# H-Bridge_Motor_Control_v01.net
KiCad netlist of a schematic drawn in EAGLE
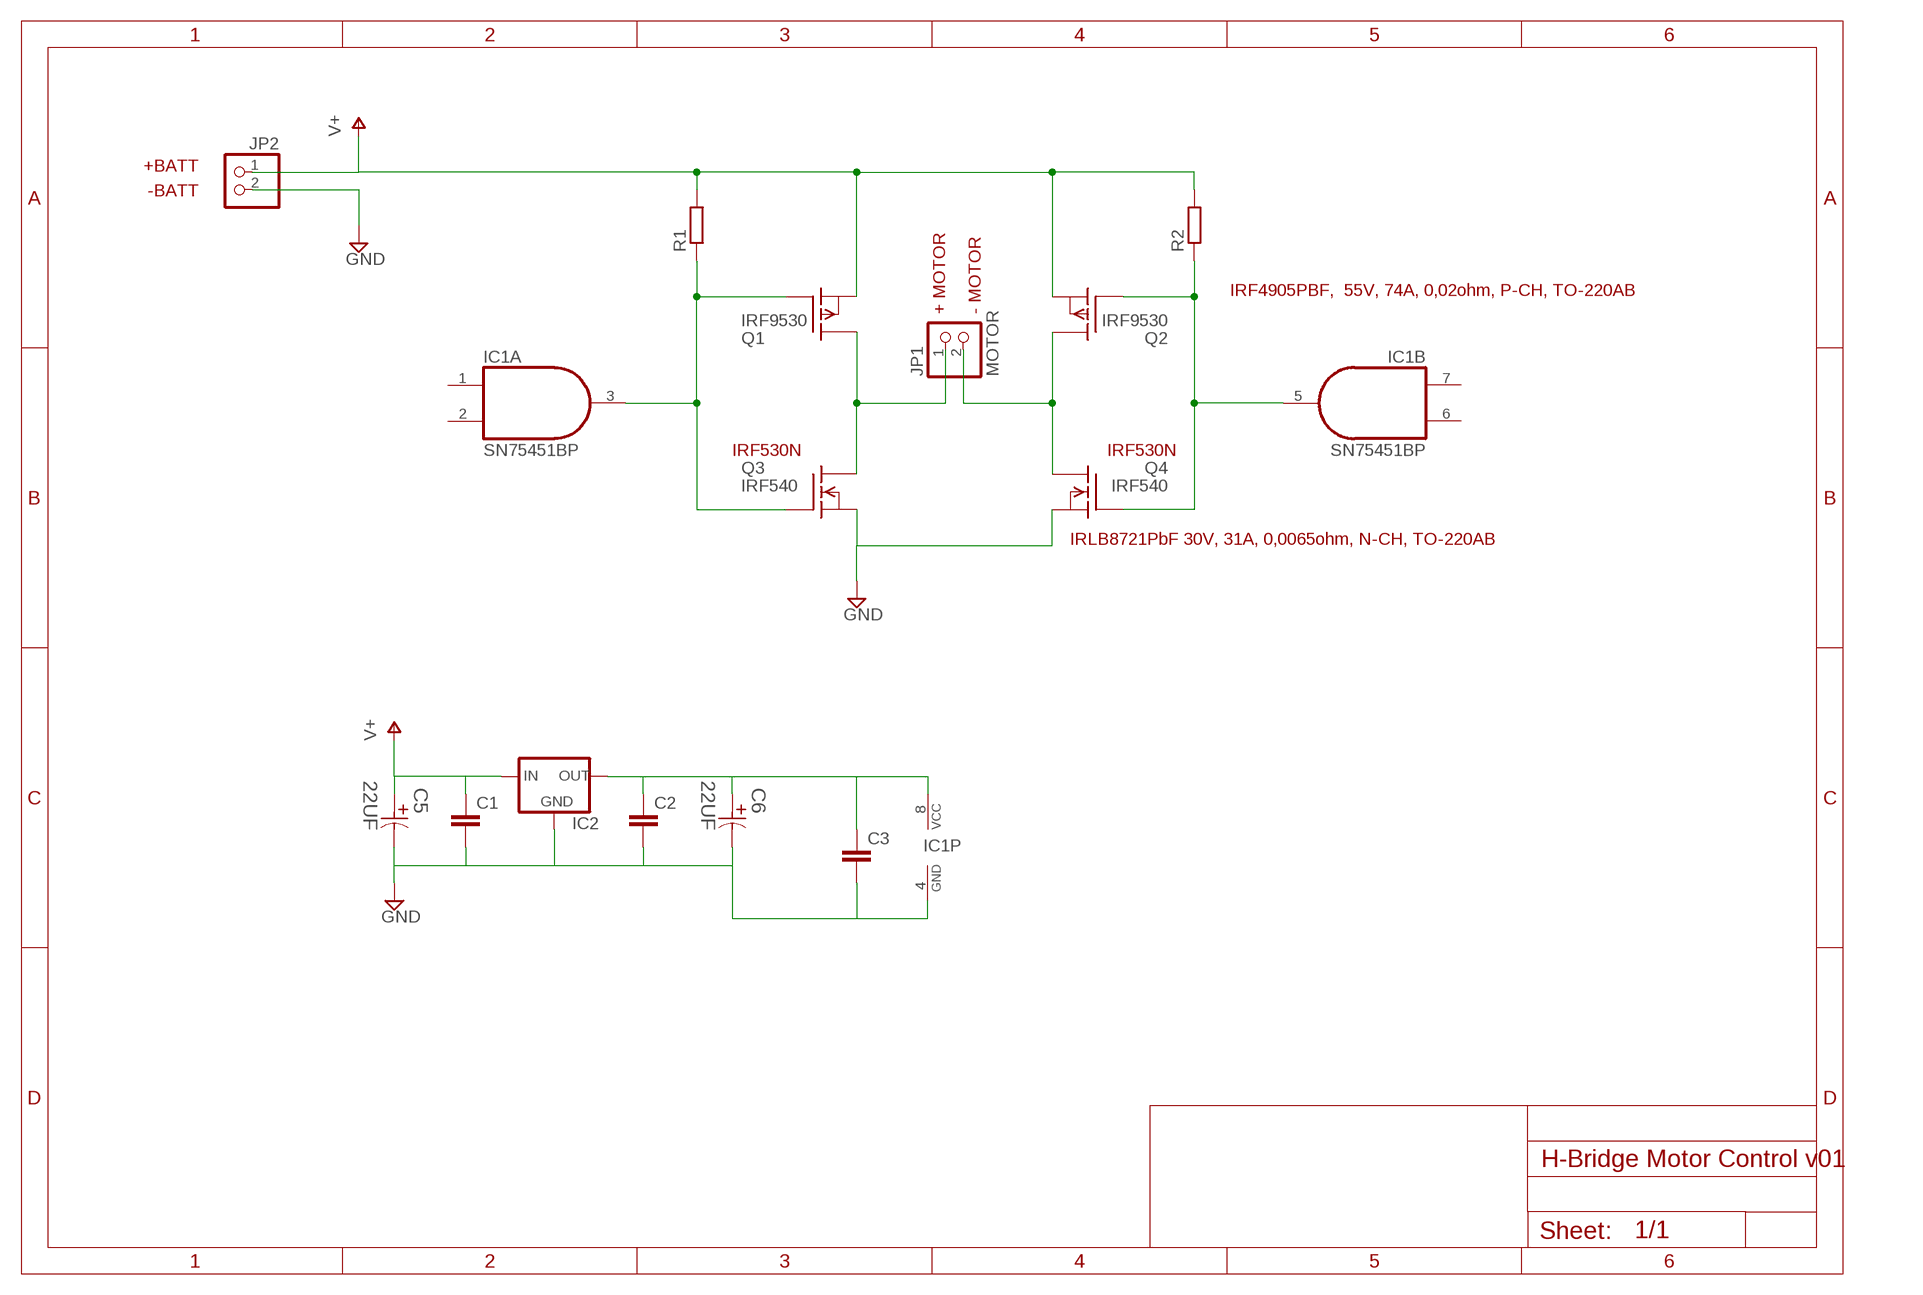
[diagram p0: schematic, sheet 1]

(export (version "E")
  (design (tool "Eeschema 10.0.6"))
  (components
    (comp (ref "C1")
      (value "C5/5")
      (footprint "eagle-import:C5B5")
      (libsource (lib "eagle-import") (part "C5/5"))
    )
    (comp (ref "C2")
      (value "C5/5")
      (footprint "eagle-import:C5B5")
      (libsource (lib "eagle-import") (part "C5/5"))
    )
    (comp (ref "C3")
      (value "C5/5")
      (footprint "eagle-import:C5B5")
      (libsource (lib "eagle-import") (part "C5/5"))
    )
    (comp (ref "C5")
      (value "22UF")
      (footprint "eagle-import:CAPPR200-500X1100")
      (fields (field (name "MPN") "ECA1EAK220X") (field (name "TOLERANCE") "±20 %"))
      (libsource (lib "eagle-import") (part "ECA-D5XP21EAK220X"))
    )
    (comp (ref "C6")
      (value "22UF")
      (footprint "eagle-import:CAPPR200-500X1100")
      (fields (field (name "MPN") "ECA1EAK220X") (field (name "TOLERANCE") "±20 %"))
      (libsource (lib "eagle-import") (part "ECA-D5XP21EAK220X"))
    )
    (comp (ref "IC1")
      (value "SN75451BP")
      (footprint "eagle-import:DIL08")
      (libsource (lib "eagle-import") (part "SN75451BP"))
    )
    (comp (ref "IC2")
      (value "78XXL")
      (footprint "eagle-import:78XXL")
      (libsource (lib "eagle-import") (part "78XXL"))
    )
    (comp (ref "JP1")
      (value "MOTOR")
      (footprint "eagle-import:1X02")
      (libsource (lib "eagle-import") (part "PINHD-1X2"))
    )
    (comp (ref "JP2")
      (value "PINHD-1X2")
      (footprint "eagle-import:1X02")
      (libsource (lib "eagle-import") (part "PINHD-1X2"))
    )
    (comp (ref "Q1")
      (value "IRF9530")
      (footprint "eagle-import:TO220")
      (libsource (lib "eagle-import") (part "IRF9530"))
    )
    (comp (ref "Q2")
      (value "IRF9530")
      (footprint "eagle-import:TO220")
      (libsource (lib "eagle-import") (part "IRF9530"))
    )
    (comp (ref "Q3")
      (value "IRF540")
      (footprint "eagle-import:TO220")
      (libsource (lib "eagle-import") (part "IRF540"))
    )
    (comp (ref "Q4")
      (value "IRF540")
      (footprint "eagle-import:TO220")
      (libsource (lib "eagle-import") (part "IRF540"))
    )
    (comp (ref "R1")
      (value "R-EU_0207/10")
      (footprint "eagle-import:0207_10")
      (libsource (lib "eagle-import") (part "R-EU_0207/10"))
    )
    (comp (ref "R2")
      (value "R-EU_0207/10")
      (footprint "eagle-import:0207_10")
      (libsource (lib "eagle-import") (part "R-EU_0207/10"))
    )
  )
  (nets
    (net (code "1") (name "GND") (class "Default")
      (node (ref "C1") (pin "2") (pinfunction "2_2") (pintype "passive"))
      (node (ref "C2") (pin "2") (pinfunction "2_2") (pintype "passive"))
      (node (ref "C3") (pin "2") (pinfunction "2_2") (pintype "passive"))
      (node (ref "C5") (pin "2") (pinfunction "2_2") (pintype "passive"))
      (node (ref "C6") (pin "2") (pinfunction "2_2") (pintype "passive"))
      (node (ref "IC1") (pin "4") (pinfunction "GND_4") (pintype "power_in"))
      (node (ref "IC2") (pin "GND") (pinfunction "GND_GND") (pintype "input"))
      (node (ref "JP2") (pin "2") (pinfunction "2_2") (pintype "passive"))
      (node (ref "Q3") (pin "3") (pinfunction "S_3") (pintype "passive"))
      (node (ref "Q4") (pin "3") (pinfunction "S_3") (pintype "passive"))
    )
    (net (code "2") (name "Net-(IC1A-O)") (class "Default")
      (node (ref "IC1") (pin "3") (pinfunction "O_3") (pintype "output"))
      (node (ref "Q1") (pin "1") (pinfunction "G_1") (pintype "passive"))
      (node (ref "Q3") (pin "1") (pinfunction "G_1") (pintype "passive"))
      (node (ref "R1") (pin "1") (pinfunction "1_1") (pintype "passive"))
    )
    (net (code "3") (name "Net-(IC1B-O)") (class "Default")
      (node (ref "IC1") (pin "5") (pinfunction "O_5") (pintype "output"))
      (node (ref "Q2") (pin "1") (pinfunction "G_1") (pintype "passive"))
      (node (ref "Q4") (pin "1") (pinfunction "G_1") (pintype "passive"))
      (node (ref "R2") (pin "1") (pinfunction "1_1") (pintype "passive"))
    )
    (net (code "4") (name "Net-(IC1C-VCC)") (class "Default")
      (node (ref "C2") (pin "1") (pinfunction "1_1") (pintype "passive"))
      (node (ref "C3") (pin "1") (pinfunction "1_1") (pintype "passive"))
      (node (ref "C6") (pin "1") (pinfunction "1_1") (pintype "passive"))
      (node (ref "IC1") (pin "8") (pinfunction "VCC_8") (pintype "power_in"))
      (node (ref "IC2") (pin "OUT") (pinfunction "OUT_OUT") (pintype "passive"))
    )
    (net (code "5") (name "Net-(Q1-D)") (class "Default")
      (node (ref "JP1") (pin "1") (pinfunction "1_1") (pintype "passive"))
      (node (ref "Q1") (pin "2") (pinfunction "D_2") (pintype "passive"))
      (node (ref "Q3") (pin "2") (pinfunction "D_2") (pintype "passive"))
    )
    (net (code "6") (name "Net-(Q2-D)") (class "Default")
      (node (ref "JP1") (pin "2") (pinfunction "2_2") (pintype "passive"))
      (node (ref "Q2") (pin "2") (pinfunction "D_2") (pintype "passive"))
      (node (ref "Q4") (pin "2") (pinfunction "D_2") (pintype "passive"))
    )
    (net (code "7") (name "V+") (class "Default")
      (node (ref "C1") (pin "1") (pinfunction "1_1") (pintype "passive"))
      (node (ref "C5") (pin "1") (pinfunction "1_1") (pintype "passive"))
      (node (ref "IC2") (pin "IN") (pinfunction "IN_IN") (pintype "input"))
      (node (ref "JP2") (pin "1") (pinfunction "1_1") (pintype "passive"))
      (node (ref "Q1") (pin "3") (pinfunction "S_3") (pintype "passive"))
      (node (ref "Q2") (pin "3") (pinfunction "S_3") (pintype "passive"))
      (node (ref "R1") (pin "2") (pinfunction "2_2") (pintype "passive"))
      (node (ref "R2") (pin "2") (pinfunction "2_2") (pintype "passive"))
    )
    (net (code "8") (name "unconnected-(IC1A-I0-Pad1)") (class "Default")
      (node (ref "IC1") (pin "1") (pinfunction "I0_1") (pintype "input"))
    )
    (net (code "9") (name "unconnected-(IC1A-I1-Pad2)") (class "Default")
      (node (ref "IC1") (pin "2") (pinfunction "I1_2") (pintype "input"))
    )
    (net (code "10") (name "unconnected-(IC1B-I0-Pad7)") (class "Default")
      (node (ref "IC1") (pin "7") (pinfunction "I0_7") (pintype "input"))
    )
    (net (code "11") (name "unconnected-(IC1B-I1-Pad6)") (class "Default")
      (node (ref "IC1") (pin "6") (pinfunction "I1_6") (pintype "input"))
    )
  )
)
